# PCB_EnergyMonitor.net
KiCad netlist of a schematic drawn in Altium Designer
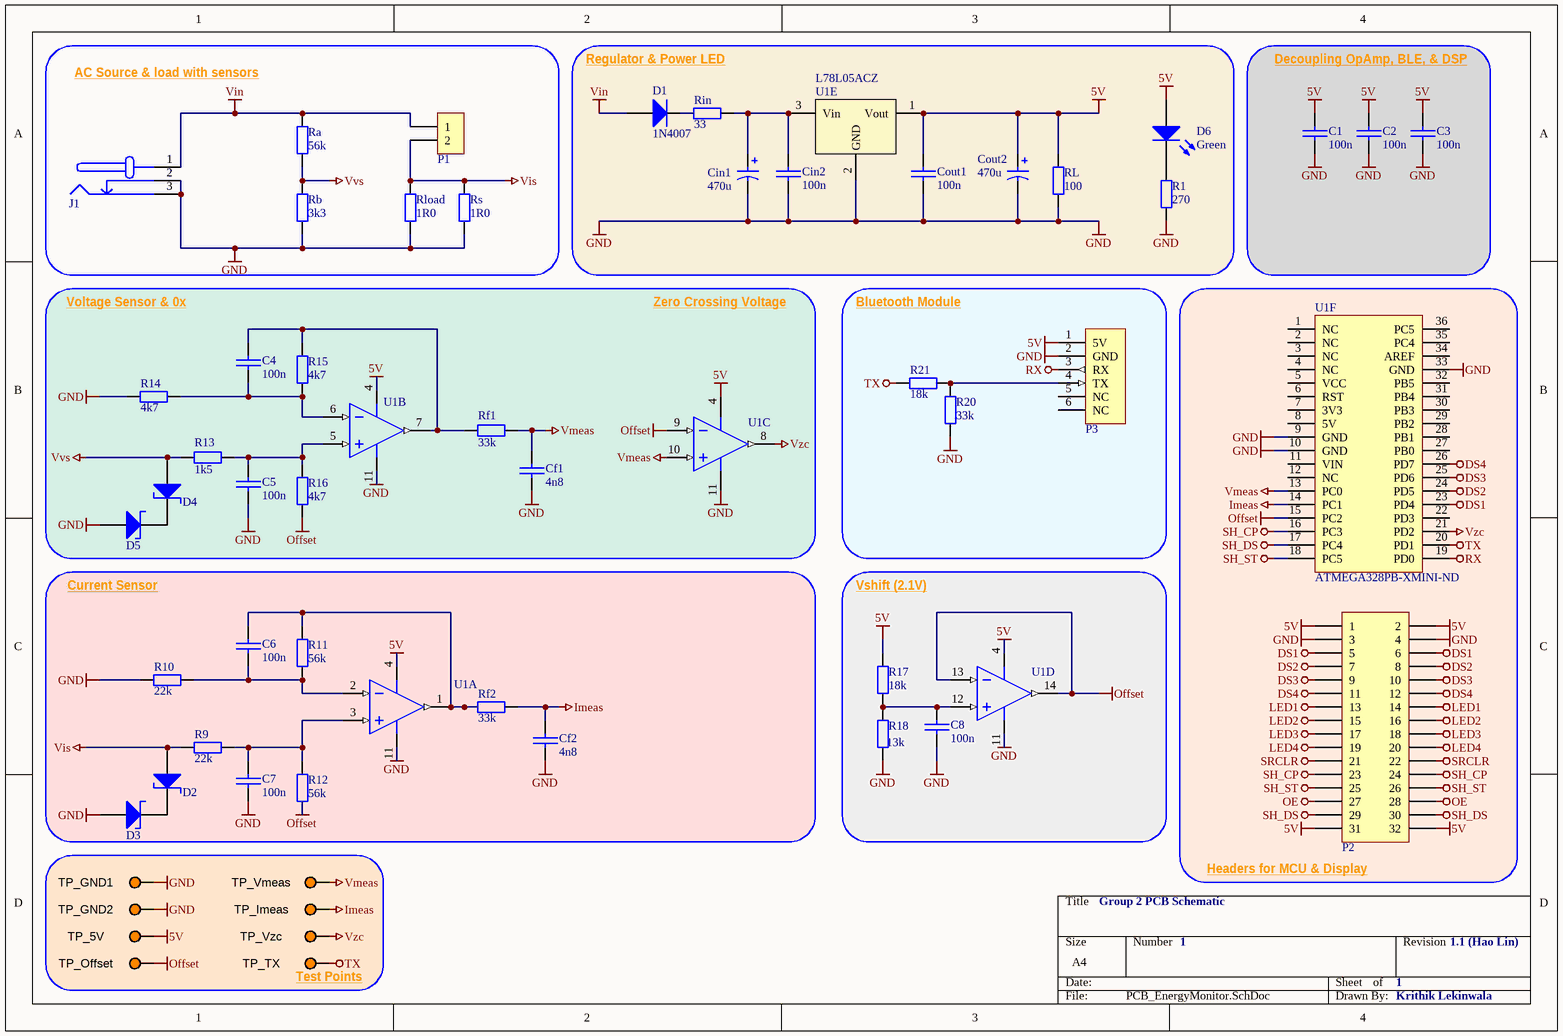
[diagram p0: PCB_EnergyMonitor.SchDoc]

(export (version "E")
  (design (tool "Eeschema 10.0.6"))
  (components
    (comp (ref "C1")
      (value "100n")
      (footprint "CCAP-5P0")
      (description "SMT ceramic capacitor 0805 size")
      (libsource (lib "EE209_Library") (part "CerCap_TH_5P0"))
    )
    (comp (ref "C2")
      (value "100n")
      (footprint "CCAP-5P0")
      (description "SMT ceramic capacitor 0805 size")
      (libsource (lib "EE209_Library") (part "CerCap_TH_5P0"))
    )
    (comp (ref "C3")
      (value "100n")
      (footprint "CCAP-5P0")
      (description "SMT ceramic capacitor 0805 size")
      (libsource (lib "EE209_Library") (part "CerCap_TH_5P0"))
    )
    (comp (ref "C4")
      (value "100n")
      (footprint "CCAP-5P0")
      (description "SMT ceramic capacitor 0805 size")
      (libsource (lib "EE209_Library") (part "CerCap_TH_5P0"))
    )
    (comp (ref "C5")
      (value "100n")
      (footprint "CCAP-5P0")
      (description "SMT ceramic capacitor 0805 size")
      (libsource (lib "EE209_Library") (part "CerCap_TH_5P0"))
    )
    (comp (ref "C6")
      (value "100n")
      (footprint "CCAP-5P0")
      (description "SMT ceramic capacitor 0805 size")
      (libsource (lib "EE209_Library") (part "CerCap_TH_5P0"))
    )
    (comp (ref "C7")
      (value "100n")
      (footprint "CCAP-5P0")
      (description "SMT ceramic capacitor 0805 size")
      (libsource (lib "EE209_Library") (part "CerCap_TH_5P0"))
    )
    (comp (ref "C8")
      (value "100n")
      (footprint "CCAP-5P0")
      (description "SMT ceramic capacitor 0805 size")
      (libsource (lib "EE209_Library") (part "CerCap_TH_5P0"))
    )
    (comp (ref "Cf1")
      (value "4n8")
      (footprint "CCAP-5P0")
      (description "SMT ceramic capacitor 0805 size")
      (libsource (lib "EE209_Library") (part "CerCap_TH_5P0"))
    )
    (comp (ref "Cf2")
      (value "4n8")
      (footprint "CCAP-5P0")
      (description "SMT ceramic capacitor 0805 size")
      (libsource (lib "EE209_Library") (part "CerCap_TH_5P0"))
    )
    (comp (ref "Cin1")
      (value "470u")
      (footprint "CAP-RAD-2.5mm Pitch")
      (description "Electrolytic capacitor with radial package, 2mm pitch and 5.2mm diameter")
      (fields (field (name "PUBLISHER") "Altium Limited"))
      (libsource (lib "EE209_Library") (part "ElecCap_TH_2P0"))
    )
    (comp (ref "Cin2")
      (value "100n")
      (footprint "CCAP-5P0")
      (description "SMT ceramic capacitor 0805 size")
      (libsource (lib "EE209_Library") (part "CerCap_TH_5P0"))
    )
    (comp (ref "Cout1")
      (value "100n")
      (footprint "CCAP-5P0")
      (description "SMT ceramic capacitor 0805 size")
      (libsource (lib "EE209_Library") (part "CerCap_TH_5P0"))
    )
    (comp (ref "Cout2")
      (value "470u")
      (footprint "CAP-RAD-2.5mm Pitch")
      (description "Electrolytic capacitor with radial package, 2mm pitch and 5.2mm diameter")
      (fields (field (name "PUBLISHER") "Altium Limited"))
      (libsource (lib "EE209_Library") (part "ElecCap_TH_2P0"))
    )
    (comp (ref "D1")
      (value "1N4007")
      (footprint "1N4007-MFG")
      (description "1N4007 1000V standard axial diode")
      (libsource (lib "EE209_Library") (part "1N4007_TH_4AX0"))
    )
    (comp (ref "D2")
      (value "BZX79-CXVX")
      (footprint "AXIAL-Zener-0.4")
      (description "Axial zener diode BZX79 series")
      (fields
        (field (name "MANUFACTURER") "Nexperia USA Inc.")
        (field (name "MANUFACTURER PART NUMBER") "BZX79-C4V7,143")
      )
      (libsource (lib "EE209_Library") (part "Zener_TH_4AX0"))
    )
    (comp (ref "D3")
      (value "BZX79-CXVX")
      (footprint "AXIAL-Zener-0.4")
      (description "Axial zener diode BZX79 series")
      (fields
        (field (name "MANUFACTURER") "Nexperia USA Inc.")
        (field (name "MANUFACTURER PART NUMBER") "BZX79-C4V7,143")
      )
      (libsource (lib "EE209_Library") (part "Zener_TH_4AX0"))
    )
    (comp (ref "D4")
      (value "BZX79-CXVX")
      (footprint "AXIAL-Zener-0.4")
      (description "Axial zener diode BZX79 series")
      (fields
        (field (name "MANUFACTURER") "Nexperia USA Inc.")
        (field (name "MANUFACTURER PART NUMBER") "BZX79-C4V7,143")
      )
      (libsource (lib "EE209_Library") (part "Zener_TH_4AX0"))
    )
    (comp (ref "D5")
      (value "BZX79-CXVX")
      (footprint "AXIAL-Zener-0.4")
      (description "Axial zener diode BZX79 series")
      (fields
        (field (name "MANUFACTURER") "Nexperia USA Inc.")
        (field (name "MANUFACTURER PART NUMBER") "BZX79-C4V7,143")
      )
      (libsource (lib "EE209_Library") (part "Zener_TH_4AX0"))
    )
    (comp (ref "D6")
      (value "Green")
      (footprint "LED")
      (description "Typical throughole GaAs LED with 2.54mm pitch")
      (fields (field (name "MANUFACTURER") "Generic Components") (field (name "PUBLISHER") "Altium Limited"))
      (libsource (lib "EE209_Library") (part "LED_TH_2P54"))
    )
    (comp (ref "J1")
      (value "DC barrel jack")
      (footprint "AC-Socket")
      (description "DC barrel jack connection to AC source")
      (libsource (lib "EE209_Library") (part "AC_Input"))
    )
    (comp (ref "P1")
      (value "Dual Banana Plugs")
      (footprint "Dual Banana Plug")
      (description "Dual banana plugs connection to the AC load")
      (fields (field (name "PUBLISHER") "Altium Limited"))
      (libsource (lib "EE209_Library") (part "AC_Output"))
    )
    (comp (ref "P2")
      (value "Display")
      (footprint "Display")
      (description "16-Pin Header Connecting Display")
      (libsource (lib "EE209_Library") (part "Display"))
    )
    (comp (ref "P3")
      (value "BLE Module Header")
      (footprint "HM10_HDR1X6")
      (description "2.54mm pitch 6-pin header for BLE module")
      (fields (field (name "PUBLISHER") "Altium Limited"))
      (libsource (lib "EE209_Library") (part "BLEModule_TH"))
    )
    (comp (ref "R1")
      (value "270")
      (footprint "AXIAL-0.4")
      (description "Through hole resistor")
      (fields (field (name "PUBLISHER") "Altium Limited"))
      (libsource (lib "EE209_Library") (part "Res_TH_0AX4"))
    )
    (comp (ref "R9")
      (value "22k")
      (footprint "AXIAL-0.4")
      (description "Through hole resistor")
      (fields (field (name "PUBLISHER") "Altium Limited"))
      (libsource (lib "") (part "Res_TH_0AX4_1"))
    )
    (comp (ref "R10")
      (value "22k")
      (footprint "AXIAL-0.4")
      (description "Through hole resistor")
      (fields (field (name "PUBLISHER") "Altium Limited"))
      (libsource (lib "") (part "Res_TH_0AX4_1"))
    )
    (comp (ref "R11")
      (value "56k")
      (footprint "AXIAL-0.4")
      (description "Through hole resistor")
      (fields (field (name "PUBLISHER") "Altium Limited"))
      (libsource (lib "EE209_Library") (part "Res_TH_0AX4"))
    )
    (comp (ref "R12")
      (value "56k")
      (footprint "AXIAL-0.4")
      (description "Through hole resistor")
      (fields (field (name "PUBLISHER") "Altium Limited"))
      (libsource (lib "EE209_Library") (part "Res_TH_0AX4"))
    )
    (comp (ref "R13")
      (value "1k5")
      (footprint "AXIAL-0.4")
      (description "Through hole resistor")
      (fields (field (name "PUBLISHER") "Altium Limited"))
      (libsource (lib "") (part "Res_TH_0AX4_1"))
    )
    (comp (ref "R14")
      (value "4k7")
      (footprint "AXIAL-0.4")
      (description "Through hole resistor")
      (fields (field (name "PUBLISHER") "Altium Limited"))
      (libsource (lib "") (part "Res_TH_0AX4_1"))
    )
    (comp (ref "R15")
      (value "4k7")
      (footprint "AXIAL-0.4")
      (description "Through hole resistor")
      (fields (field (name "PUBLISHER") "Altium Limited"))
      (libsource (lib "EE209_Library") (part "Res_TH_0AX4"))
    )
    (comp (ref "R16")
      (value "4k7")
      (footprint "AXIAL-0.4")
      (description "Through hole resistor")
      (fields (field (name "PUBLISHER") "Altium Limited"))
      (libsource (lib "EE209_Library") (part "Res_TH_0AX4"))
    )
    (comp (ref "R17")
      (value "18k")
      (footprint "AXIAL-0.4")
      (description "Through hole resistor")
      (fields (field (name "PUBLISHER") "Altium Limited"))
      (libsource (lib "EE209_Library") (part "Res_TH_0AX4"))
    )
    (comp (ref "R18")
      (value "13k")
      (footprint "AXIAL-0.4")
      (description "Through hole resistor")
      (fields (field (name "PUBLISHER") "Altium Limited"))
      (libsource (lib "EE209_Library") (part "Res_TH_0AX4"))
    )
    (comp (ref "R20")
      (value "33k")
      (footprint "AXIAL-0.4")
      (description "Through hole resistor")
      (fields (field (name "PUBLISHER") "Altium Limited"))
      (libsource (lib "EE209_Library") (part "Res_TH_0AX4"))
    )
    (comp (ref "R21")
      (value "18k")
      (footprint "AXIAL-0.4")
      (description "Through hole resistor")
      (fields (field (name "PUBLISHER") "Altium Limited"))
      (libsource (lib "") (part "Res_TH_0AX4_3"))
    )
    (comp (ref "Ra")
      (value "56k")
      (footprint "AXIAL-0.4")
      (description "Through hole resistor")
      (fields (field (name "PUBLISHER") "Altium Limited"))
      (libsource (lib "EE209_Library") (part "Res_TH_0AX4"))
    )
    (comp (ref "Rb")
      (value "3k3")
      (footprint "AXIAL-0.4")
      (description "Through hole resistor")
      (fields (field (name "PUBLISHER") "Altium Limited"))
      (libsource (lib "EE209_Library") (part "Res_TH_0AX4"))
    )
    (comp (ref "Rf1")
      (value "33k")
      (footprint "AXIAL-0.4")
      (description "Through hole resistor")
      (fields (field (name "PUBLISHER") "Altium Limited"))
      (libsource (lib "") (part "Res_TH_0AX4_1"))
    )
    (comp (ref "Rf2")
      (value "33k")
      (footprint "AXIAL-0.4")
      (description "Through hole resistor")
      (fields (field (name "PUBLISHER") "Altium Limited"))
      (libsource (lib "") (part "Res_TH_0AX4_1"))
    )
    (comp (ref "Rin")
      (value "33")
      (footprint "AXIAL-0.4")
      (description "Through hole resistor")
      (fields (field (name "PUBLISHER") "Altium Limited"))
      (libsource (lib "") (part "Res_TH_0AX4_1"))
    )
    (comp (ref "RL")
      (value "100")
      (footprint "AXIAL-0.4")
      (description "Through hole resistor")
      (fields (field (name "PUBLISHER") "Altium Limited"))
      (libsource (lib "EE209_Library") (part "Res_TH_0AX4"))
    )
    (comp (ref "Rload")
      (value "1R0")
      (footprint "AXIAL-0.4")
      (description "Through hole resistor")
      (fields (field (name "PUBLISHER") "Altium Limited"))
      (libsource (lib "EE209_Library") (part "Res_TH_0AX4"))
    )
    (comp (ref "Rs")
      (value "1R0")
      (footprint "AXIAL-0.4")
      (description "Through hole resistor")
      (fields (field (name "PUBLISHER") "Altium Limited"))
      (libsource (lib "") (part "Res_TH_0AX4_2"))
    )
    (comp (ref "TP_5V")
      (value "5003")
      (footprint "TP_TH")
      (description "Test Point, Orange, 1-Pin THD, RoHS")
      (libsource (lib "EE209_Library") (part "TestPoint"))
    )
    (comp (ref "TP_GND1")
      (value "5003")
      (footprint "TP_TH")
      (description "Test Point, Orange, 1-Pin THD, RoHS")
      (libsource (lib "EE209_Library") (part "TestPoint"))
    )
    (comp (ref "TP_GND2")
      (value "5003")
      (footprint "TP_TH")
      (description "Test Point, Orange, 1-Pin THD, RoHS")
      (libsource (lib "EE209_Library") (part "TestPoint"))
    )
    (comp (ref "TP_Imeas")
      (value "5003")
      (footprint "TP_TH")
      (description "Test Point, Orange, 1-Pin THD, RoHS")
      (libsource (lib "EE209_Library") (part "TestPoint"))
    )
    (comp (ref "TP_Offset")
      (value "5003")
      (footprint "TP_TH")
      (description "Test Point, Orange, 1-Pin THD, RoHS")
      (libsource (lib "EE209_Library") (part "TestPoint"))
    )
    (comp (ref "TP_TX")
      (value "5003")
      (footprint "TP_TH")
      (description "Test Point, Orange, 1-Pin THD, RoHS")
      (libsource (lib "EE209_Library") (part "TestPoint"))
    )
    (comp (ref "TP_Vmeas")
      (value "5003")
      (footprint "TP_TH")
      (description "Test Point, Orange, 1-Pin THD, RoHS")
      (libsource (lib "EE209_Library") (part "TestPoint"))
    )
    (comp (ref "TP_Vzc")
      (value "5003")
      (footprint "TP_TH")
      (description "Test Point, Orange, 1-Pin THD, RoHS")
      (libsource (lib "EE209_Library") (part "TestPoint"))
    )
    (comp (ref "U1")
      (value "LM324")
      (footprint "DIP-14")
      (description "IC OPAMP GP 14DIP")
      (fields
        (field (name "MANUFACTURER") "ON Semiconductor")
        (field (name "MANUFACTURER PART NUMBER") "LM324N")
      )
      (libsource (lib "EE209_Library") (part "LM324N_TH_DIP16"))
    )
    (comp (ref "U1E")
      (value "L78L05ACZ")
      (footprint "TO-92")
      (description "Voltage Regulator 5V")
      (fields
        (field (name "MANUFACTURER") "ON Semiconductor")
        (field (name "MANUFACTURER PART NUMBER") "LM78L05ACZX")
      )
      (libsource (lib "EE209_Library") (part "L78L05_TH_TO92"))
    )
    (comp (ref "U1F")
      (value "ATmega328PB Xplained Mini Header")
      (footprint "ATmeg328P Xplained")
      (description "Dual 18-pin headers connecting to ATmega328PB Xplained Mini")
      (fields
        (field (name "MANUFACTURER") "Microchip Technology")
        (field (name "MANUFACTURER PART NUMBER") "ATMEGA328PB-XMINI")
        (field (name "SUPPLIER PART NUMBER 1") "ATMEGA328PB-XMINI-ND")
      )
      (libsource (lib "EE209_Library") (part "ATmega328PBXplained_TH"))
    )
  )
  (nets
    (net (code "1") (name "5V") (class "Default")
      (node (ref "C1") (pin "1") (pinfunction "1_1") (pintype "passive"))
      (node (ref "C2") (pin "1") (pinfunction "1_1") (pintype "passive"))
      (node (ref "C3") (pin "1") (pinfunction "1_1") (pintype "passive"))
      (node (ref "Cout1") (pin "1") (pinfunction "1_1") (pintype "passive"))
      (node (ref "Cout2") (pin "1") (pinfunction "1_1") (pintype "passive"))
      (node (ref "D6") (pin "1") (pinfunction "A_1") (pintype "passive"))
      (node (ref "P2") (pin "1") (pinfunction "1_1") (pintype "passive"))
      (node (ref "P2") (pin "2") (pinfunction "2_2") (pintype "passive"))
      (node (ref "P2") (pin "31") (pinfunction "31_31") (pintype "passive"))
      (node (ref "P2") (pin "32") (pinfunction "32_32") (pintype "passive"))
      (node (ref "P3") (pin "1") (pinfunction "5V_1") (pintype "passive"))
      (node (ref "R17") (pin "2") (pinfunction "2_2") (pintype "passive"))
      (node (ref "RL") (pin "2") (pinfunction "2_2") (pintype "passive"))
      (node (ref "TP_5V") (pin "1") (pinfunction "1_1") (pintype "passive"))
      (node (ref "U1") (pin "4") (pinfunction "VDD_4") (pintype "power_in"))
      (node (ref "U1E") (pin "1") (pinfunction "Vout_1") (pintype "passive"))
    )
    (net (code "2") (name "DS1") (class "Default")
      (node (ref "P2") (pin "5") (pinfunction "5_5") (pintype "passive"))
      (node (ref "P2") (pin "6") (pinfunction "6_6") (pintype "passive"))
      (node (ref "U1F") (pin "23") (pinfunction "PD4_23") (pintype "passive"))
    )
    (net (code "3") (name "DS2") (class "Default")
      (node (ref "P2") (pin "7") (pinfunction "7_7") (pintype "passive"))
      (node (ref "P2") (pin "8") (pinfunction "8_8") (pintype "passive"))
      (node (ref "U1F") (pin "24") (pinfunction "PD5_24") (pintype "passive"))
    )
    (net (code "4") (name "DS3") (class "Default")
      (node (ref "P2") (pin "10") (pinfunction "10_10") (pintype "passive"))
      (node (ref "P2") (pin "9") (pinfunction "9_9") (pintype "passive"))
      (node (ref "U1F") (pin "25") (pinfunction "PD6_25") (pintype "passive"))
    )
    (net (code "5") (name "DS4") (class "Default")
      (node (ref "P2") (pin "11") (pinfunction "11_11") (pintype "passive"))
      (node (ref "P2") (pin "12") (pinfunction "12_12") (pintype "passive"))
      (node (ref "U1F") (pin "26") (pinfunction "PD7_26") (pintype "passive"))
    )
    (net (code "6") (name "GND") (class "Default")
      (node (ref "C1") (pin "2") (pinfunction "2_2") (pintype "passive"))
      (node (ref "C2") (pin "2") (pinfunction "2_2") (pintype "passive"))
      (node (ref "C3") (pin "2") (pinfunction "2_2") (pintype "passive"))
      (node (ref "C5") (pin "2") (pinfunction "2_2") (pintype "passive"))
      (node (ref "C7") (pin "2") (pinfunction "2_2") (pintype "passive"))
      (node (ref "C8") (pin "2") (pinfunction "2_2") (pintype "passive"))
      (node (ref "Cf1") (pin "2") (pinfunction "2_2") (pintype "passive"))
      (node (ref "Cf2") (pin "2") (pinfunction "2_2") (pintype "passive"))
      (node (ref "Cin1") (pin "2") (pinfunction "2_2") (pintype "passive"))
      (node (ref "Cin2") (pin "2") (pinfunction "2_2") (pintype "passive"))
      (node (ref "Cout1") (pin "2") (pinfunction "2_2") (pintype "passive"))
      (node (ref "Cout2") (pin "2") (pinfunction "2_2") (pintype "passive"))
      (node (ref "D3") (pin "1") (pinfunction "A_1") (pintype "passive"))
      (node (ref "D5") (pin "1") (pinfunction "A_1") (pintype "passive"))
      (node (ref "J1") (pin "2") (pinfunction "GND_ALT_2") (pintype "power_in"))
      (node (ref "J1") (pin "3") (pinfunction "GND_3") (pintype "power_in"))
      (node (ref "P2") (pin "3") (pinfunction "3_3") (pintype "passive"))
      (node (ref "P2") (pin "4") (pinfunction "4_4") (pintype "passive"))
      (node (ref "P3") (pin "2") (pinfunction "GND_2") (pintype "passive"))
      (node (ref "R1") (pin "1") (pinfunction "1_1") (pintype "passive"))
      (node (ref "R10") (pin "1") (pinfunction "1_1") (pintype "passive"))
      (node (ref "R14") (pin "1") (pinfunction "1_1") (pintype "passive"))
      (node (ref "R18") (pin "1") (pinfunction "1_1") (pintype "passive"))
      (node (ref "R20") (pin "1") (pinfunction "1_1") (pintype "passive"))
      (node (ref "RL") (pin "1") (pinfunction "1_1") (pintype "passive"))
      (node (ref "Rb") (pin "1") (pinfunction "1_1") (pintype "passive"))
      (node (ref "Rload") (pin "1") (pinfunction "1_1") (pintype "passive"))
      (node (ref "Rs") (pin "2") (pinfunction "2_2") (pintype "passive"))
      (node (ref "TP_GND1") (pin "1") (pinfunction "1_1") (pintype "passive"))
      (node (ref "TP_GND2") (pin "1") (pinfunction "1_1") (pintype "passive"))
      (node (ref "U1") (pin "11") (pinfunction "VSS_11") (pintype "power_in"))
      (node (ref "U1E") (pin "2") (pinfunction "GND_2") (pintype "passive"))
      (node (ref "U1F") (pin "10") (pinfunction "GND_10") (pintype "power_in"))
      (node (ref "U1F") (pin "33") (pinfunction "GND_33") (pintype "passive"))
      (node (ref "U1F") (pin "9") (pinfunction "GND_9") (pintype "power_in"))
    )
    (net (code "7") (name "Imeas") (class "Default")
      (node (ref "Cf2") (pin "1") (pinfunction "1_1") (pintype "passive"))
      (node (ref "Rf2") (pin "2") (pinfunction "2_2") (pintype "passive"))
      (node (ref "TP_Imeas") (pin "1") (pinfunction "1_1") (pintype "passive"))
      (node (ref "U1F") (pin "14") (pinfunction "PC1_14") (pintype "passive"))
    )
    (net (code "8") (name "LED1") (class "Default")
      (node (ref "P2") (pin "13") (pinfunction "13_13") (pintype "passive"))
      (node (ref "P2") (pin "14") (pinfunction "14_14") (pintype "passive"))
    )
    (net (code "9") (name "LED2") (class "Default")
      (node (ref "P2") (pin "15") (pinfunction "15_15") (pintype "passive"))
      (node (ref "P2") (pin "16") (pinfunction "16_16") (pintype "passive"))
    )
    (net (code "10") (name "LED3") (class "Default")
      (node (ref "P2") (pin "17") (pinfunction "17_17") (pintype "passive"))
      (node (ref "P2") (pin "18") (pinfunction "18_18") (pintype "passive"))
    )
    (net (code "11") (name "LED4") (class "Default")
      (node (ref "P2") (pin "19") (pinfunction "19_19") (pintype "passive"))
      (node (ref "P2") (pin "20") (pinfunction "20_20") (pintype "passive"))
    )
    (net (code "12") (name "Net-(D1-K)") (class "Default")
      (node (ref "D1") (pin "2") (pinfunction "K_2") (pintype "passive"))
      (node (ref "Rin") (pin "1") (pinfunction "1_1") (pintype "passive"))
    )
    (net (code "13") (name "Net-(D2-K)") (class "Default")
      (node (ref "D2") (pin "2") (pinfunction "K_2") (pintype "passive"))
      (node (ref "D3") (pin "2") (pinfunction "K_2") (pintype "passive"))
    )
    (net (code "14") (name "Net-(D4-K)") (class "Default")
      (node (ref "D4") (pin "2") (pinfunction "K_2") (pintype "passive"))
      (node (ref "D5") (pin "2") (pinfunction "K_2") (pintype "passive"))
    )
    (net (code "15") (name "Net-(D6-K)") (class "Default")
      (node (ref "D6") (pin "2") (pinfunction "K_2") (pintype "passive"))
      (node (ref "R1") (pin "2") (pinfunction "2_2") (pintype "passive"))
    )
    (net (code "16") (name "Net-(P3-TX)") (class "Default")
      (node (ref "P3") (pin "4") (pinfunction "TX_4") (pintype "input"))
      (node (ref "R20") (pin "2") (pinfunction "2_2") (pintype "passive"))
      (node (ref "R21") (pin "1") (pinfunction "1_1") (pintype "passive"))
    )
    (net (code "17") (name "Net-(U1A-VINA+)") (class "Default")
      (node (ref "C7") (pin "1") (pinfunction "1_1") (pintype "passive"))
      (node (ref "R12") (pin "2") (pinfunction "2_2") (pintype "passive"))
      (node (ref "R9") (pin "2") (pinfunction "2_2") (pintype "passive"))
      (node (ref "U1") (pin "3") (pinfunction "VINA+_3") (pintype "input"))
    )
    (net (code "18") (name "Net-(U1A-VINA-)") (class "Default")
      (node (ref "C6") (pin "2") (pinfunction "2_2") (pintype "passive"))
      (node (ref "R10") (pin "2") (pinfunction "2_2") (pintype "passive"))
      (node (ref "R11") (pin "1") (pinfunction "1_1") (pintype "passive"))
      (node (ref "U1") (pin "2") (pinfunction "VINA-_2") (pintype "input"))
    )
    (net (code "19") (name "Net-(U1A-VOUTA)") (class "Default")
      (node (ref "C6") (pin "1") (pinfunction "1_1") (pintype "passive"))
      (node (ref "R11") (pin "2") (pinfunction "2_2") (pintype "passive"))
      (node (ref "Rf2") (pin "1") (pinfunction "1_1") (pintype "passive"))
      (node (ref "U1") (pin "1") (pinfunction "VOUTA_1") (pintype "output"))
    )
    (net (code "20") (name "Net-(U1B-VINB+)") (class "Default")
      (node (ref "C5") (pin "1") (pinfunction "1_1") (pintype "passive"))
      (node (ref "R13") (pin "2") (pinfunction "2_2") (pintype "passive"))
      (node (ref "R16") (pin "2") (pinfunction "2_2") (pintype "passive"))
      (node (ref "U1") (pin "5") (pinfunction "VINB+_5") (pintype "input"))
    )
    (net (code "21") (name "Net-(U1B-VINB-)") (class "Default")
      (node (ref "C4") (pin "2") (pinfunction "2_2") (pintype "passive"))
      (node (ref "R14") (pin "2") (pinfunction "2_2") (pintype "passive"))
      (node (ref "R15") (pin "1") (pinfunction "1_1") (pintype "passive"))
      (node (ref "U1") (pin "6") (pinfunction "VINB-_6") (pintype "input"))
    )
    (net (code "22") (name "Net-(U1B-VOUTB)") (class "Default")
      (node (ref "C4") (pin "1") (pinfunction "1_1") (pintype "passive"))
      (node (ref "R15") (pin "2") (pinfunction "2_2") (pintype "passive"))
      (node (ref "Rf1") (pin "1") (pinfunction "1_1") (pintype "passive"))
      (node (ref "U1") (pin "7") (pinfunction "VOUTB_7") (pintype "output"))
    )
    (net (code "23") (name "Net-(U1D-VIND+)") (class "Default")
      (node (ref "C8") (pin "1") (pinfunction "1_1") (pintype "passive"))
      (node (ref "R17") (pin "1") (pinfunction "1_1") (pintype "passive"))
      (node (ref "R18") (pin "2") (pinfunction "2_2") (pintype "passive"))
      (node (ref "U1") (pin "12") (pinfunction "VIND+_12") (pintype "input"))
    )
    (net (code "24") (name "Net-(U1E-Vin)") (class "Default")
      (node (ref "Cin1") (pin "1") (pinfunction "1_1") (pintype "passive"))
      (node (ref "Cin2") (pin "1") (pinfunction "1_1") (pintype "passive"))
      (node (ref "Rin") (pin "2") (pinfunction "2_2") (pintype "passive"))
      (node (ref "U1E") (pin "3") (pinfunction "Vin_3") (pintype "passive"))
    )
    (net (code "25") (name "OE") (class "Default")
      (node (ref "P2") (pin "27") (pinfunction "27_27") (pintype "passive"))
      (node (ref "P2") (pin "28") (pinfunction "28_28") (pintype "passive"))
    )
    (net (code "26") (name "Offset") (class "Default")
      (node (ref "R12") (pin "1") (pinfunction "1_1") (pintype "passive"))
      (node (ref "R16") (pin "1") (pinfunction "1_1") (pintype "passive"))
      (node (ref "TP_Offset") (pin "1") (pinfunction "1_1") (pintype "passive"))
      (node (ref "U1") (pin "13") (pinfunction "VIND-_13") (pintype "input"))
      (node (ref "U1") (pin "14") (pinfunction "VOUTD_14") (pintype "output"))
      (node (ref "U1") (pin "9") (pinfunction "VINC-_9") (pintype "input"))
      (node (ref "U1F") (pin "15") (pinfunction "PC2_15") (pintype "passive"))
    )
    (net (code "27") (name "RX") (class "Default")
      (node (ref "P3") (pin "3") (pinfunction "RX_3") (pintype "output"))
      (node (ref "U1F") (pin "19") (pinfunction "PD0_19") (pintype "passive"))
    )
    (net (code "28") (name "SH_CP") (class "Default")
      (node (ref "P2") (pin "23") (pinfunction "23_23") (pintype "passive"))
      (node (ref "P2") (pin "24") (pinfunction "24_24") (pintype "passive"))
      (node (ref "U1F") (pin "16") (pinfunction "PC3_16") (pintype "passive"))
    )
    (net (code "29") (name "SH_DS") (class "Default")
      (node (ref "P2") (pin "29") (pinfunction "29_29") (pintype "passive"))
      (node (ref "P2") (pin "30") (pinfunction "30_30") (pintype "passive"))
      (node (ref "U1F") (pin "17") (pinfunction "PC4_17") (pintype "passive"))
    )
    (net (code "30") (name "SH_ST") (class "Default")
      (node (ref "P2") (pin "25") (pinfunction "25_25") (pintype "passive"))
      (node (ref "P2") (pin "26") (pinfunction "26_26") (pintype "passive"))
      (node (ref "U1F") (pin "18") (pinfunction "PC5_18") (pintype "passive"))
    )
    (net (code "31") (name "SRCLR") (class "Default")
      (node (ref "P2") (pin "21") (pinfunction "21_21") (pintype "passive"))
      (node (ref "P2") (pin "22") (pinfunction "22_22") (pintype "passive"))
    )
    (net (code "32") (name "TX") (class "Default")
      (node (ref "R21") (pin "2") (pinfunction "2_2") (pintype "passive"))
      (node (ref "TP_TX") (pin "1") (pinfunction "1_1") (pintype "passive"))
      (node (ref "U1F") (pin "20") (pinfunction "PD1_20") (pintype "passive"))
    )
    (net (code "33") (name "Vin") (class "Default")
      (node (ref "D1") (pin "1") (pinfunction "A_1") (pintype "passive"))
      (node (ref "J1") (pin "1") (pinfunction "VCC_1") (pintype "power_in"))
      (node (ref "P1") (pin "1") (pinfunction "1_1") (pintype "passive"))
      (node (ref "Ra") (pin "2") (pinfunction "2_2") (pintype "passive"))
    )
    (net (code "34") (name "Vis") (class "Default")
      (node (ref "D2") (pin "1") (pinfunction "A_1") (pintype "passive"))
      (node (ref "P1") (pin "2") (pinfunction "2_2") (pintype "passive"))
      (node (ref "R9") (pin "1") (pinfunction "1_1") (pintype "passive"))
      (node (ref "Rload") (pin "2") (pinfunction "2_2") (pintype "passive"))
      (node (ref "Rs") (pin "1") (pinfunction "1_1") (pintype "passive"))
    )
    (net (code "35") (name "Vmeas") (class "Default")
      (node (ref "Cf1") (pin "1") (pinfunction "1_1") (pintype "passive"))
      (node (ref "Rf1") (pin "2") (pinfunction "2_2") (pintype "passive"))
      (node (ref "TP_Vmeas") (pin "1") (pinfunction "1_1") (pintype "passive"))
      (node (ref "U1") (pin "10") (pinfunction "VINC+_10") (pintype "input"))
      (node (ref "U1F") (pin "13") (pinfunction "PC0_13") (pintype "passive"))
    )
    (net (code "36") (name "Vvs") (class "Default")
      (node (ref "D4") (pin "1") (pinfunction "A_1") (pintype "passive"))
      (node (ref "R13") (pin "1") (pinfunction "1_1") (pintype "passive"))
      (node (ref "Ra") (pin "1") (pinfunction "1_1") (pintype "passive"))
      (node (ref "Rb") (pin "2") (pinfunction "2_2") (pintype "passive"))
    )
    (net (code "37") (name "Vzc") (class "Default")
      (node (ref "TP_Vzc") (pin "1") (pinfunction "1_1") (pintype "passive"))
      (node (ref "U1") (pin "8") (pinfunction "VOUTC_8") (pintype "output"))
      (node (ref "U1F") (pin "21") (pinfunction "PD2_21") (pintype "passive"))
    )
    (net (code "38") (name "unconnected-(P3-NC-Pad5)") (class "Default")
      (node (ref "P3") (pin "5") (pinfunction "NC_5") (pintype "passive"))
    )
    (net (code "39") (name "unconnected-(P3-NC-Pad6)") (class "Default")
      (node (ref "P3") (pin "6") (pinfunction "NC_6") (pintype "passive"))
    )
    (net (code "40") (name "unconnected-(U1C-VDD-Pad4)") (class "Default")
      (node (ref "U1") (pin "4") (pinfunction "VDD_4") (pintype "power_in"))
    )
    (net (code "41") (name "unconnected-(U1C-VSS-Pad11)") (class "Default")
      (node (ref "U1") (pin "11") (pinfunction "VSS_11") (pintype "power_in"))
    )
    (net (code "42") (name "unconnected-(U1F-3V3-Pad7)") (class "Default")
      (node (ref "U1F") (pin "7") (pinfunction "3V3_7") (pintype "passive"))
    )
    (net (code "43") (name "unconnected-(U1F-5V-Pad8)") (class "Default")
      (node (ref "U1F") (pin "8") (pinfunction "5V_8") (pintype "power_in"))
    )
    (net (code "44") (name "unconnected-(U1F-AREF-Pad34)") (class "Default")
      (node (ref "U1F") (pin "34") (pinfunction "AREF_34") (pintype "passive"))
    )
    (net (code "45") (name "unconnected-(U1F-NC-Pad1)") (class "Default")
      (node (ref "U1F") (pin "1") (pinfunction "NC_1") (pintype "passive"))
    )
    (net (code "46") (name "unconnected-(U1F-NC-Pad2)") (class "Default")
      (node (ref "U1F") (pin "2") (pinfunction "NC_2") (pintype "passive"))
    )
    (net (code "47") (name "unconnected-(U1F-NC-Pad3)") (class "Default")
      (node (ref "U1F") (pin "3") (pinfunction "NC_3") (pintype "passive"))
    )
    (net (code "48") (name "unconnected-(U1F-NC-Pad4)") (class "Default")
      (node (ref "U1F") (pin "4") (pinfunction "NC_4") (pintype "passive"))
    )
    (net (code "49") (name "unconnected-(U1F-NC-Pad12)") (class "Default")
      (node (ref "U1F") (pin "12") (pinfunction "NC_12") (pintype "passive"))
    )
    (net (code "50") (name "unconnected-(U1F-PB0-Pad27)") (class "Default")
      (node (ref "U1F") (pin "27") (pinfunction "PB0_27") (pintype "passive"))
    )
    (net (code "51") (name "unconnected-(U1F-PB1-Pad28)") (class "Default")
      (node (ref "U1F") (pin "28") (pinfunction "PB1_28") (pintype "passive"))
    )
    (net (code "52") (name "unconnected-(U1F-PB2-Pad29)") (class "Default")
      (node (ref "U1F") (pin "29") (pinfunction "PB2_29") (pintype "passive"))
    )
    (net (code "53") (name "unconnected-(U1F-PB3-Pad30)") (class "Default")
      (node (ref "U1F") (pin "30") (pinfunction "PB3_30") (pintype "passive"))
    )
    (net (code "54") (name "unconnected-(U1F-PB4-Pad31)") (class "Default")
      (node (ref "U1F") (pin "31") (pinfunction "PB4_31") (pintype "passive"))
    )
    (net (code "55") (name "unconnected-(U1F-PB5-Pad32)") (class "Default")
      (node (ref "U1F") (pin "32") (pinfunction "PB5_32") (pintype "passive"))
    )
    (net (code "56") (name "unconnected-(U1F-PC4-Pad35)") (class "Default")
      (node (ref "U1F") (pin "35") (pinfunction "PC4_35") (pintype "passive"))
    )
    (net (code "57") (name "unconnected-(U1F-PC5-Pad36)") (class "Default")
      (node (ref "U1F") (pin "36") (pinfunction "PC5_36") (pintype "passive"))
    )
    (net (code "58") (name "unconnected-(U1F-PD3-Pad22)") (class "Default")
      (node (ref "U1F") (pin "22") (pinfunction "PD3_22") (pintype "passive"))
    )
    (net (code "59") (name "unconnected-(U1F-RST-Pad6)") (class "Default")
      (node (ref "U1F") (pin "6") (pinfunction "RST_6") (pintype "passive"))
    )
    (net (code "60") (name "unconnected-(U1F-VCC-Pad5)") (class "Default")
      (node (ref "U1F") (pin "5") (pinfunction "VCC_5") (pintype "power_in"))
    )
    (net (code "61") (name "unconnected-(U1F-VIN-Pad11)") (class "Default")
      (node (ref "U1F") (pin "11") (pinfunction "VIN_11") (pintype "power_in"))
    )
  )
)
